# Enclosure_Front_NusbioPlus.net
KiCad netlist of a schematic drawn in EAGLE
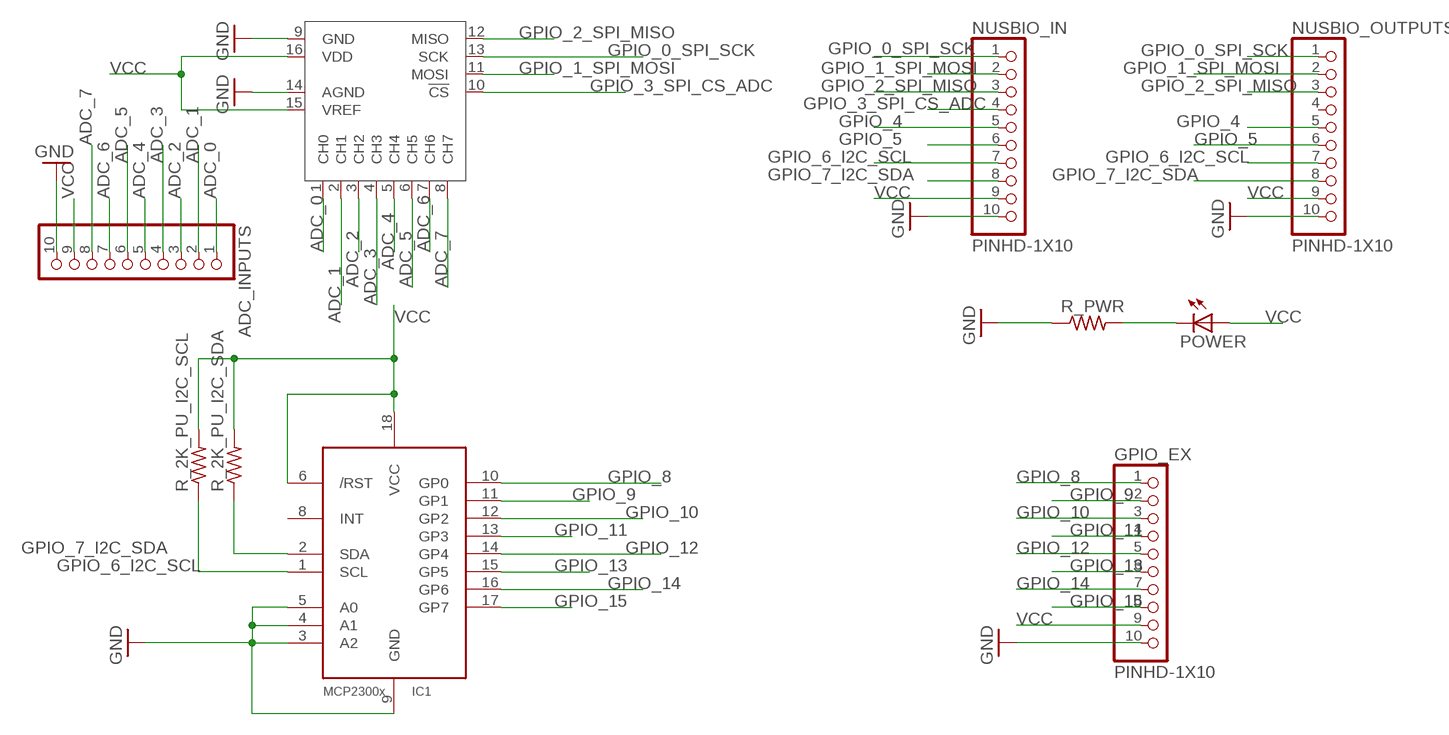
[diagram p0: schematic, sheet 1]

(export (version "E")
  (design (tool "Eeschema 10.0.6"))
  (components
    (comp (ref "ADC_INPUTS")
      (value "PINHD-1X10")
      (footprint "eagle-import:1X10-BIG")
      (libsource (lib "eagle-import") (part "PINHD-1X10"))
    )
    (comp (ref "GPIO_EX")
      (value "PINHD-1X10")
      (footprint "eagle-import:1X10-BIG")
      (libsource (lib "eagle-import") (part "PINHD-1X10"))
    )
    (comp (ref "IC1")
      (value "MCP23008/SO")
      (footprint "eagle-import:SO18W")
      (libsource (lib "eagle-import") (part "MCP23008/SO"))
    )
    (comp (ref "NUSBIO_IN")
      (value "PINHD-1X10")
      (footprint "eagle-import:1X10-BIG")
      (libsource (lib "eagle-import") (part "PINHD-1X10"))
    )
    (comp (ref "NUSBIO_OUTPUTS")
      (value "PINHD-1X10")
      (footprint "eagle-import:1X10-BIG")
      (libsource (lib "eagle-import") (part "PINHD-1X10"))
    )
    (comp (ref "POWER")
      (value "LEDSMT1206")
      (footprint "eagle-import:1206")
      (libsource (lib "eagle-import") (part "LEDSMT1206"))
    )
    (comp (ref "R_2K_PU_I2C_SCL")
      (value "R-US_R1206")
      (footprint "eagle-import:R1206")
      (libsource (lib "eagle-import") (part "R-US_R1206"))
    )
    (comp (ref "R_2K_PU_I2C_SDA")
      (value "R-US_R1206")
      (footprint "eagle-import:R1206")
      (libsource (lib "eagle-import") (part "R-US_R1206"))
    )
    (comp (ref "R_PWR")
      (value "R-US_R1206")
      (footprint "eagle-import:R1206")
      (libsource (lib "eagle-import") (part "R-US_R1206"))
    )
    (comp (ref "U$1")
      (value "MCP3008SL")
      (footprint "eagle-import:SO16")
      (libsource (lib "eagle-import") (part "MCP3008SL"))
    )
  )
  (nets
    (net (code "1") (name "/ADC_0") (class "Default")
      (node (ref "ADC_INPUTS") (pin "1") (pinfunction "1_1") (pintype "passive"))
      (node (ref "U$1") (pin "1") (pinfunction "CH0_1") (pintype "input"))
    )
    (net (code "2") (name "/ADC_1") (class "Default")
      (node (ref "ADC_INPUTS") (pin "2") (pinfunction "2_2") (pintype "passive"))
      (node (ref "U$1") (pin "2") (pinfunction "CH1_2") (pintype "input"))
    )
    (net (code "3") (name "/ADC_2") (class "Default")
      (node (ref "ADC_INPUTS") (pin "3") (pinfunction "3_3") (pintype "passive"))
      (node (ref "U$1") (pin "3") (pinfunction "CH2_3") (pintype "input"))
    )
    (net (code "4") (name "/ADC_3") (class "Default")
      (node (ref "ADC_INPUTS") (pin "4") (pinfunction "4_4") (pintype "passive"))
      (node (ref "U$1") (pin "4") (pinfunction "CH3_4") (pintype "input"))
    )
    (net (code "5") (name "/ADC_4") (class "Default")
      (node (ref "ADC_INPUTS") (pin "5") (pinfunction "5_5") (pintype "passive"))
      (node (ref "U$1") (pin "5") (pinfunction "CH4_5") (pintype "input"))
    )
    (net (code "6") (name "/ADC_5") (class "Default")
      (node (ref "ADC_INPUTS") (pin "6") (pinfunction "6_6") (pintype "passive"))
      (node (ref "U$1") (pin "6") (pinfunction "CH5_6") (pintype "input"))
    )
    (net (code "7") (name "/ADC_6") (class "Default")
      (node (ref "ADC_INPUTS") (pin "7") (pinfunction "7_7") (pintype "passive"))
      (node (ref "U$1") (pin "7") (pinfunction "CH6_7") (pintype "input"))
    )
    (net (code "8") (name "/ADC_7") (class "Default")
      (node (ref "ADC_INPUTS") (pin "8") (pinfunction "8_8") (pintype "passive"))
      (node (ref "U$1") (pin "8") (pinfunction "CH7_8") (pintype "input"))
    )
    (net (code "9") (name "/GPIO_0_SPI_SCK") (class "Default")
      (node (ref "NUSBIO_IN") (pin "1") (pinfunction "1_1") (pintype "passive"))
      (node (ref "NUSBIO_OUTPUTS") (pin "1") (pinfunction "1_1") (pintype "passive"))
      (node (ref "U$1") (pin "13") (pinfunction "SCK_13") (pintype "input"))
    )
    (net (code "10") (name "/GPIO_1_SPI_MOSI") (class "Default")
      (node (ref "NUSBIO_IN") (pin "2") (pinfunction "2_2") (pintype "passive"))
      (node (ref "NUSBIO_OUTPUTS") (pin "2") (pinfunction "2_2") (pintype "passive"))
      (node (ref "U$1") (pin "11") (pinfunction "MOSI_11") (pintype "input"))
    )
    (net (code "11") (name "/GPIO_2_SPI_MISO") (class "Default")
      (node (ref "NUSBIO_IN") (pin "3") (pinfunction "3_3") (pintype "passive"))
      (node (ref "NUSBIO_OUTPUTS") (pin "3") (pinfunction "3_3") (pintype "passive"))
      (node (ref "U$1") (pin "12") (pinfunction "MISO_12") (pintype "output"))
    )
    (net (code "12") (name "/GPIO_3_SPI_CS_ADC") (class "Default")
      (node (ref "NUSBIO_IN") (pin "4") (pinfunction "4_4") (pintype "passive"))
      (node (ref "U$1") (pin "10") (pinfunction "~{CS}_10") (pintype "input"))
    )
    (net (code "13") (name "/GPIO_4") (class "Default")
      (node (ref "NUSBIO_IN") (pin "5") (pinfunction "5_5") (pintype "passive"))
      (node (ref "NUSBIO_OUTPUTS") (pin "5") (pinfunction "5_5") (pintype "passive"))
    )
    (net (code "14") (name "/GPIO_5") (class "Default")
      (node (ref "NUSBIO_IN") (pin "6") (pinfunction "6_6") (pintype "passive"))
      (node (ref "NUSBIO_OUTPUTS") (pin "6") (pinfunction "6_6") (pintype "passive"))
    )
    (net (code "15") (name "/GPIO_6_I2C_SCL") (class "Default")
      (node (ref "IC1") (pin "1") (pinfunction "SCL_1") (pintype "bidirectional"))
      (node (ref "NUSBIO_IN") (pin "7") (pinfunction "7_7") (pintype "passive"))
      (node (ref "NUSBIO_OUTPUTS") (pin "7") (pinfunction "7_7") (pintype "passive"))
      (node (ref "R_2K_PU_I2C_SCL") (pin "1") (pinfunction "1_1") (pintype "passive"))
    )
    (net (code "16") (name "/GPIO_7_I2C_SDA") (class "Default")
      (node (ref "IC1") (pin "2") (pinfunction "SDA_2") (pintype "bidirectional"))
      (node (ref "NUSBIO_IN") (pin "8") (pinfunction "8_8") (pintype "passive"))
      (node (ref "NUSBIO_OUTPUTS") (pin "8") (pinfunction "8_8") (pintype "passive"))
      (node (ref "R_2K_PU_I2C_SDA") (pin "1") (pinfunction "1_1") (pintype "passive"))
    )
    (net (code "17") (name "/GPIO_8") (class "Default")
      (node (ref "GPIO_EX") (pin "1") (pinfunction "1_1") (pintype "passive"))
      (node (ref "IC1") (pin "10") (pinfunction "GP0_10") (pintype "bidirectional"))
    )
    (net (code "18") (name "/GPIO_9") (class "Default")
      (node (ref "GPIO_EX") (pin "2") (pinfunction "2_2") (pintype "passive"))
      (node (ref "IC1") (pin "11") (pinfunction "GP1_11") (pintype "bidirectional"))
    )
    (net (code "19") (name "/GPIO_10") (class "Default")
      (node (ref "GPIO_EX") (pin "3") (pinfunction "3_3") (pintype "passive"))
      (node (ref "IC1") (pin "12") (pinfunction "GP2_12") (pintype "bidirectional"))
    )
    (net (code "20") (name "/GPIO_11") (class "Default")
      (node (ref "GPIO_EX") (pin "4") (pinfunction "4_4") (pintype "passive"))
      (node (ref "IC1") (pin "13") (pinfunction "GP3_13") (pintype "bidirectional"))
    )
    (net (code "21") (name "/GPIO_12") (class "Default")
      (node (ref "GPIO_EX") (pin "5") (pinfunction "5_5") (pintype "passive"))
      (node (ref "IC1") (pin "14") (pinfunction "GP4_14") (pintype "bidirectional"))
    )
    (net (code "22") (name "/GPIO_13") (class "Default")
      (node (ref "GPIO_EX") (pin "6") (pinfunction "6_6") (pintype "passive"))
      (node (ref "IC1") (pin "15") (pinfunction "GP5_15") (pintype "bidirectional"))
    )
    (net (code "23") (name "/GPIO_14") (class "Default")
      (node (ref "GPIO_EX") (pin "7") (pinfunction "7_7") (pintype "passive"))
      (node (ref "IC1") (pin "16") (pinfunction "GP6_16") (pintype "bidirectional"))
    )
    (net (code "24") (name "/GPIO_15") (class "Default")
      (node (ref "GPIO_EX") (pin "8") (pinfunction "8_8") (pintype "passive"))
      (node (ref "IC1") (pin "17") (pinfunction "GP7_17") (pintype "bidirectional"))
    )
    (net (code "25") (name "/VCC") (class "Default")
      (node (ref "ADC_INPUTS") (pin "9") (pinfunction "9_9") (pintype "passive"))
      (node (ref "GPIO_EX") (pin "9") (pinfunction "9_9") (pintype "passive"))
      (node (ref "IC1") (pin "18") (pinfunction "VCC_18") (pintype "power_in"))
      (node (ref "IC1") (pin "6") (pinfunction "/RST_6") (pintype "input"))
      (node (ref "NUSBIO_IN") (pin "9") (pinfunction "9_9") (pintype "passive"))
      (node (ref "NUSBIO_OUTPUTS") (pin "9") (pinfunction "9_9") (pintype "passive"))
      (node (ref "POWER") (pin "A") (pinfunction "A_A") (pintype "passive"))
      (node (ref "R_2K_PU_I2C_SCL") (pin "2") (pinfunction "2_2") (pintype "passive"))
      (node (ref "R_2K_PU_I2C_SDA") (pin "2") (pinfunction "2_2") (pintype "passive"))
      (node (ref "U$1") (pin "15") (pinfunction "VREF_15") (pintype "power_in"))
      (node (ref "U$1") (pin "16") (pinfunction "VDD_16") (pintype "power_in"))
    )
    (net (code "26") (name "GND") (class "Default")
      (node (ref "ADC_INPUTS") (pin "10") (pinfunction "10_10") (pintype "passive"))
      (node (ref "GPIO_EX") (pin "10") (pinfunction "10_10") (pintype "passive"))
      (node (ref "IC1") (pin "3") (pinfunction "A2_3") (pintype "input"))
      (node (ref "IC1") (pin "4") (pinfunction "A1_4") (pintype "input"))
      (node (ref "IC1") (pin "5") (pinfunction "A0_5") (pintype "input"))
      (node (ref "IC1") (pin "9") (pinfunction "GND_9") (pintype "power_in"))
      (node (ref "NUSBIO_IN") (pin "10") (pinfunction "10_10") (pintype "passive"))
      (node (ref "NUSBIO_OUTPUTS") (pin "10") (pinfunction "10_10") (pintype "passive"))
      (node (ref "R_PWR") (pin "1") (pinfunction "1_1") (pintype "passive"))
      (node (ref "U$1") (pin "14") (pinfunction "AGND_14") (pintype "power_in"))
      (node (ref "U$1") (pin "9") (pinfunction "GND_9") (pintype "power_in"))
    )
    (net (code "27") (name "Net-(POWER-PadC)") (class "Default")
      (node (ref "POWER") (pin "C") (pinfunction "C_C") (pintype "passive"))
      (node (ref "R_PWR") (pin "2") (pinfunction "2_2") (pintype "passive"))
    )
    (net (code "28") (name "unconnected-(IC1-INT-Pad8)") (class "Default")
      (node (ref "IC1") (pin "8") (pinfunction "INT_8") (pintype "output"))
    )
    (net (code "29") (name "unconnected-(NUSBIO_OUTPUTS-Pad4)") (class "Default")
      (node (ref "NUSBIO_OUTPUTS") (pin "4") (pinfunction "4_4") (pintype "passive"))
    )
  )
)
